# MCU.net
KiCad netlist of a schematic drawn in Altium Designer
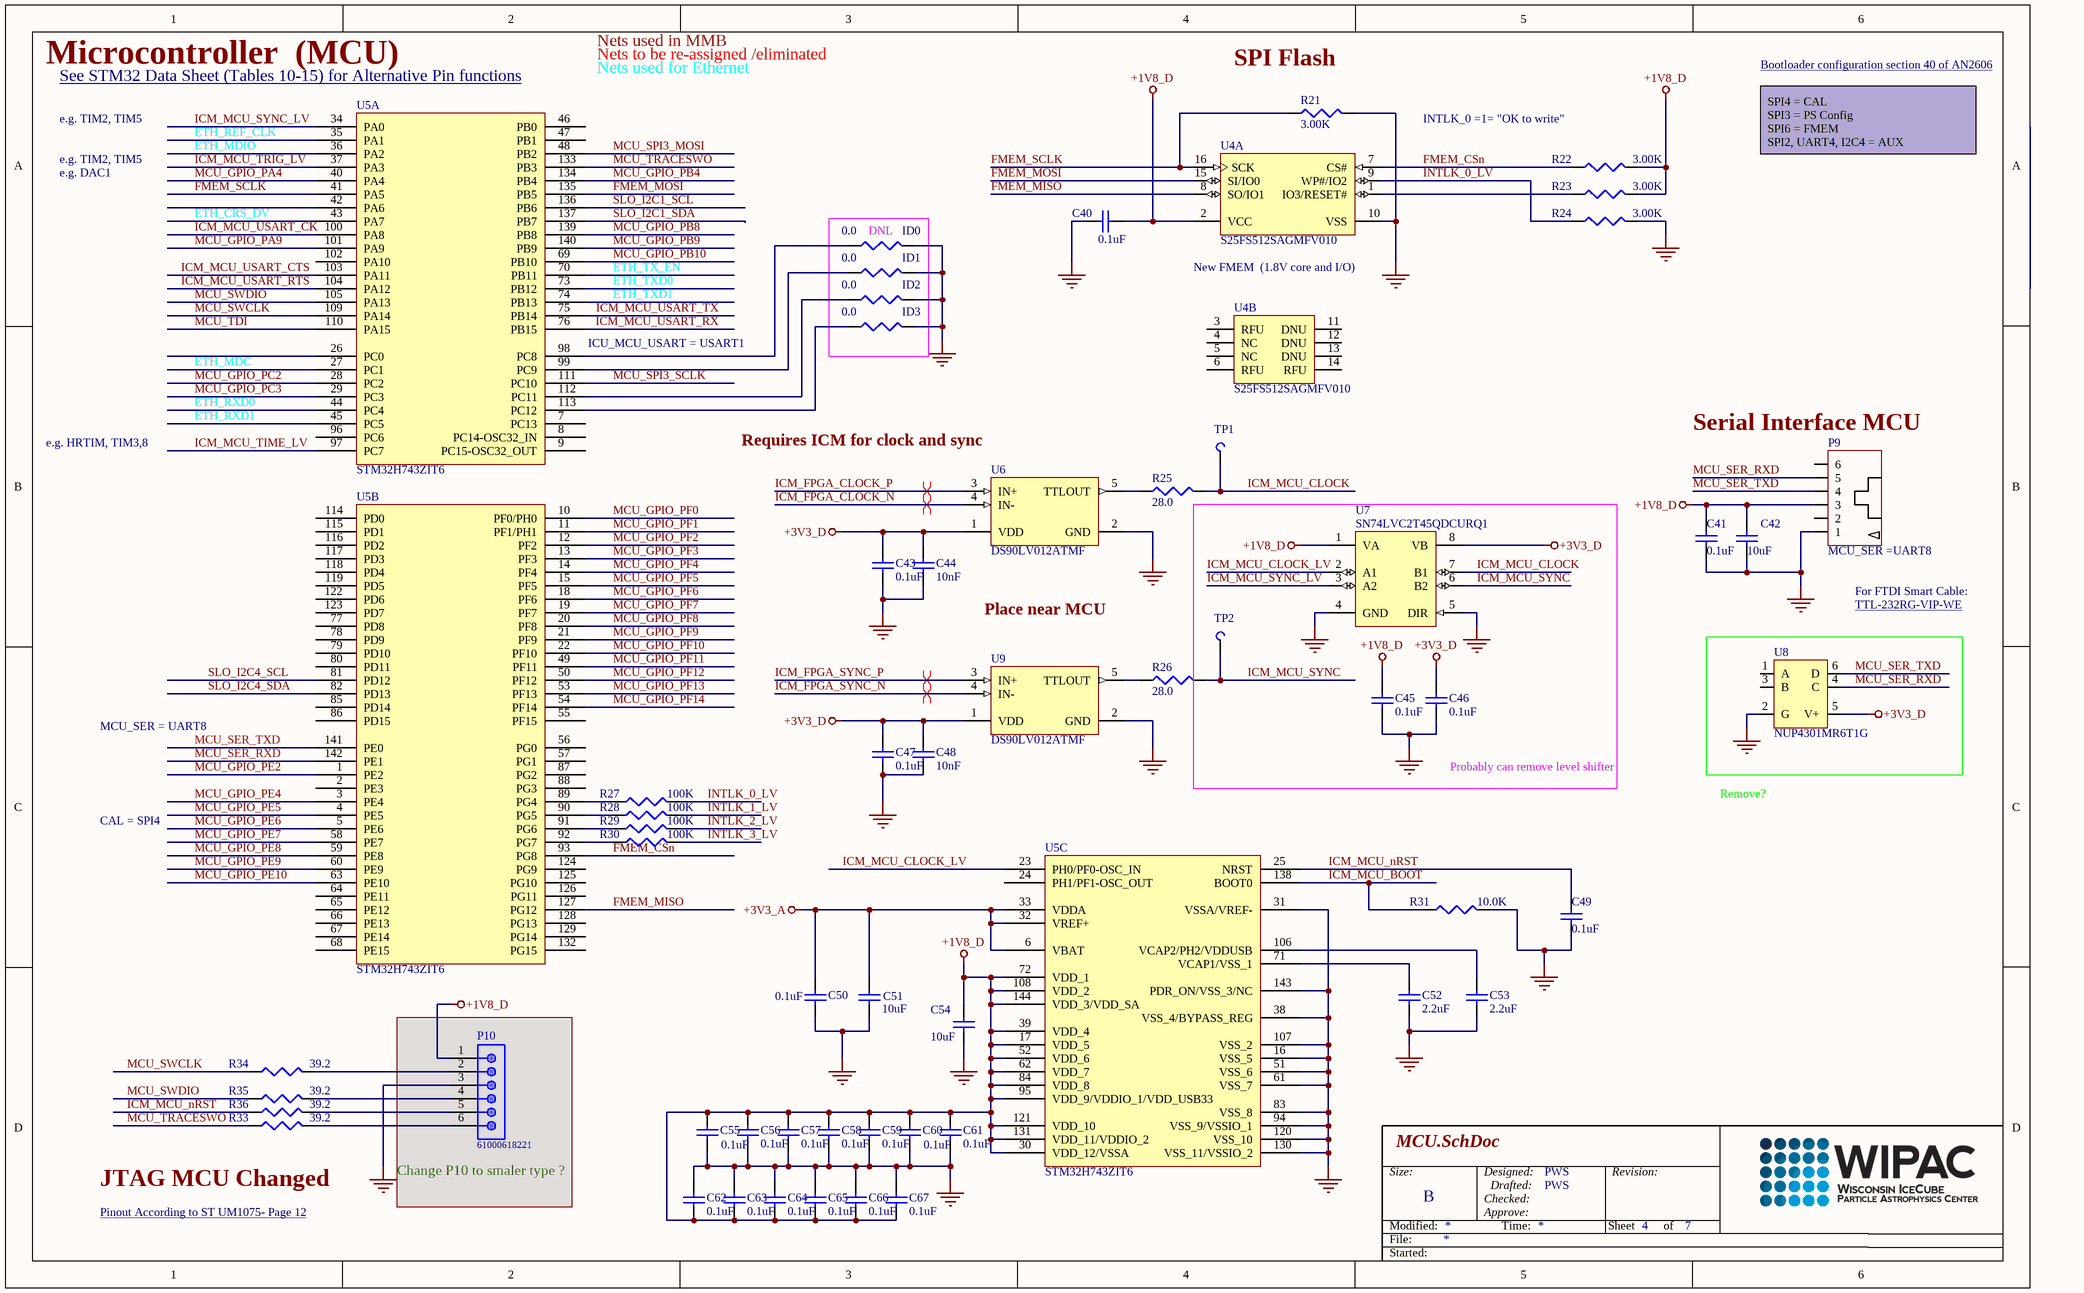
[diagram p0: MCU.SchDoc]

(export (version "E")
  (design (tool "Eeschema 10.0.6"))
  (components
    (comp (ref "C40")
      (value "0.1uF_603_50V")
      (footprint "CAPC_0603")
      (description "0.1µF ±10% 50V Ceramic Capacitor X7R 0603 (1608 Metric)")
      (fields
        (field (name "MANUFACTURER") "TDK")
        (field (name "MANUFACTURER PART NUMBER") "CGJ3E2X7R1H104K080AA")
        (field (name "CAPACITANCE") "0.1uF")
      )
      (libsource (lib "Custom1") (part "CapC_0.1uF_603_50V"))
    )
    (comp (ref "C41")
      (value "0.1uF_603_50V")
      (footprint "CAPC_0603")
      (description "0.1µF ±10% 50V Ceramic Capacitor X7R 0603 (1608 Metric)")
      (fields
        (field (name "MANUFACTURER") "Murata")
        (field (name "MANUFACTURER PART NUMBER") "GCJ188R71H104KA12D")
        (field (name "CAPACITANCE") "0.1uF")
      )
      (libsource (lib "Custom1") (part "CapC_0.1uF_603_50V_GCJ"))
    )
    (comp (ref "C42")
      (value "10uF_1206_16V")
      (footprint "CAPC_1206")
      (description "Capacitor")
      (fields
        (field (name "MANUFACTURER") "Murata")
        (field (name "MANUFACTURER PART NUMBER") "GCJ31CR71C106KA15L")
        (field (name "CAPACITANCE") "10uF")
      )
      (libsource (lib "Custom1") (part "CapC_10uF_1206_16V"))
    )
    (comp (ref "C43")
      (value "0.1uF_603_50V")
      (footprint "CAPC_0603")
      (description "0.1µF ±10% 50V Ceramic Capacitor X7R 0603 (1608 Metric)")
      (fields
        (field (name "MANUFACTURER") "TDK")
        (field (name "MANUFACTURER PART NUMBER") "CGJ3E2X7R1H104K080AA")
        (field (name "CAPACITANCE") "0.1uF")
      )
      (libsource (lib "Custom1") (part "CapC_0.1uF_603_50V"))
    )
    (comp (ref "C44")
      (value "10nF")
      (footprint "CAPC1608X90X35LL10T15")
      (description "Chip Capacitor, 10000 pF, +/- 10%, 16 V, -55 to 125 degC, 0603 (1608 Metric), RoHS, Tape and Reel")
      (fields (field (name "MANUFACTURER") "Murata"))
      (libsource (lib "Altium Content Vault") (part "CAP-NP-2"))
    )
    (comp (ref "C45")
      (value "0.1uF_603_50V")
      (footprint "CAPC_0603")
      (description "0.1µF ±10% 50V Ceramic Capacitor X7R 0603 (1608 Metric)")
      (fields
        (field (name "MANUFACTURER") "TDK")
        (field (name "MANUFACTURER PART NUMBER") "CGJ3E2X7R1H104K080AA")
        (field (name "CAPACITANCE") "0.1uF")
      )
      (libsource (lib "Custom1") (part "CapC_0.1uF_603_50V"))
    )
    (comp (ref "C46")
      (value "0.1uF_603_50V")
      (footprint "CAPC_0603")
      (description "0.1µF ±10% 50V Ceramic Capacitor X7R 0603 (1608 Metric)")
      (fields
        (field (name "MANUFACTURER") "TDK")
        (field (name "MANUFACTURER PART NUMBER") "CGJ3E2X7R1H104K080AA")
        (field (name "CAPACITANCE") "0.1uF")
      )
      (libsource (lib "Custom1") (part "CapC_0.1uF_603_50V"))
    )
    (comp (ref "C47")
      (value "0.1uF_603_50V")
      (footprint "CAPC_0603")
      (description "0.1µF ±10% 50V Ceramic Capacitor X7R 0603 (1608 Metric)")
      (fields
        (field (name "MANUFACTURER") "TDK")
        (field (name "MANUFACTURER PART NUMBER") "CGJ3E2X7R1H104K080AA")
        (field (name "CAPACITANCE") "0.1uF")
      )
      (libsource (lib "Custom1") (part "CapC_0.1uF_603_50V"))
    )
    (comp (ref "C48")
      (value "10nF")
      (footprint "CAPC1608X90X35LL10T15")
      (description "Chip Capacitor, 10000 pF, +/- 10%, 16 V, -55 to 125 degC, 0603 (1608 Metric), RoHS, Tape and Reel")
      (fields (field (name "MANUFACTURER") "Murata"))
      (libsource (lib "Altium Content Vault") (part "CAP-NP-2"))
    )
    (comp (ref "C49")
      (value "0.1uF_603_50V")
      (footprint "CAPC_0603")
      (description "0.1µF ±10% 50V Ceramic Capacitor X7R 0603 (1608 Metric)")
      (fields
        (field (name "MANUFACTURER") "Murata")
        (field (name "MANUFACTURER PART NUMBER") "GCJ188R71H104KA12D")
        (field (name "CAPACITANCE") "0.1uF")
      )
      (libsource (lib "Custom1") (part "CapC_0.1uF_603_50V_GCJ"))
    )
    (comp (ref "C50")
      (value "0.1uF_603_50V")
      (footprint "CAPC_0603")
      (description "0.1µF ±10% 50V Ceramic Capacitor X7R 0603 (1608 Metric)")
      (fields
        (field (name "MANUFACTURER") "TDK")
        (field (name "MANUFACTURER PART NUMBER") "CGJ3E2X7R1H104K080AA")
        (field (name "CAPACITANCE") "0.1uF")
      )
      (libsource (lib "Custom1") (part "CapC_0.1uF_603_50V"))
    )
    (comp (ref "C51")
      (value "10uF_805_10V")
      (footprint "CAPC_0805")
      (description "Capacitor")
      (fields
        (field (name "MANUFACTURER") "Murata")
        (field (name "MANUFACTURER PART NUMBER") "GCJ21BR71A106KE01L")
        (field (name "CAPACITANCE") "10uF")
      )
      (libsource (lib "Custom1") (part "CapC_10uF_805_10V"))
    )
    (comp (ref "C52")
      (value "2.2uF_805_16V")
      (footprint "CAPC_0805")
      (description "CAP CER 2.2UF 16V X7R 0805")
      (fields
        (field (name "MANUFACTURER") "Murata")
        (field (name "MANUFACTURER PART NUMBER") "GCJ21BR71C225KA13L")
        (field (name "CAPACITANCE") "2.2uF")
      )
      (libsource (lib "Custom1") (part "CapC_2.2uF_805_16V"))
    )
    (comp (ref "C53")
      (value "2.2uF_805_16V")
      (footprint "CAPC_0805")
      (description "CAP CER 2.2UF 16V X7R 0805")
      (fields
        (field (name "MANUFACTURER") "Murata")
        (field (name "MANUFACTURER PART NUMBER") "GCJ21BR71C225KA13L")
        (field (name "CAPACITANCE") "2.2uF")
      )
      (libsource (lib "Custom1") (part "CapC_2.2uF_805_16V"))
    )
    (comp (ref "C54")
      (value "10uF_805_10V")
      (footprint "CAPC_0805")
      (description "Capacitor")
      (fields
        (field (name "MANUFACTURER") "Murata")
        (field (name "MANUFACTURER PART NUMBER") "GCJ21BR71A106KE01L")
        (field (name "CAPACITANCE") "10uF")
      )
      (libsource (lib "Custom1") (part "CapC_10uF_805_10V"))
    )
    (comp (ref "C55")
      (value "0.1uF_603_50V")
      (footprint "CAPC_0603")
      (description "0.1µF ±10% 50V Ceramic Capacitor X7R 0603 (1608 Metric)")
      (fields
        (field (name "MANUFACTURER") "TDK")
        (field (name "MANUFACTURER PART NUMBER") "CGJ3E2X7R1H104K080AA")
        (field (name "CAPACITANCE") "0.1uF")
      )
      (libsource (lib "Custom1") (part "CapC_0.1uF_603_50V"))
    )
    (comp (ref "C56")
      (value "0.1uF_603_50V")
      (footprint "CAPC_0603")
      (description "0.1µF ±10% 50V Ceramic Capacitor X7R 0603 (1608 Metric)")
      (fields
        (field (name "MANUFACTURER") "TDK")
        (field (name "MANUFACTURER PART NUMBER") "CGJ3E2X7R1H104K080AA")
        (field (name "CAPACITANCE") "0.1uF")
      )
      (libsource (lib "Custom1") (part "CapC_0.1uF_603_50V"))
    )
    (comp (ref "C57")
      (value "0.1uF_603_50V")
      (footprint "CAPC_0603")
      (description "0.1µF ±10% 50V Ceramic Capacitor X7R 0603 (1608 Metric)")
      (fields
        (field (name "MANUFACTURER") "TDK")
        (field (name "MANUFACTURER PART NUMBER") "CGJ3E2X7R1H104K080AA")
        (field (name "CAPACITANCE") "0.1uF")
      )
      (libsource (lib "Custom1") (part "CapC_0.1uF_603_50V"))
    )
    (comp (ref "C58")
      (value "0.1uF_603_50V")
      (footprint "CAPC_0603")
      (description "0.1µF ±10% 50V Ceramic Capacitor X7R 0603 (1608 Metric)")
      (fields
        (field (name "MANUFACTURER") "TDK")
        (field (name "MANUFACTURER PART NUMBER") "CGJ3E2X7R1H104K080AA")
        (field (name "CAPACITANCE") "0.1uF")
      )
      (libsource (lib "Custom1") (part "CapC_0.1uF_603_50V"))
    )
    (comp (ref "C59")
      (value "0.1uF_603_50V")
      (footprint "CAPC_0603")
      (description "0.1µF ±10% 50V Ceramic Capacitor X7R 0603 (1608 Metric)")
      (fields
        (field (name "MANUFACTURER") "TDK")
        (field (name "MANUFACTURER PART NUMBER") "CGJ3E2X7R1H104K080AA")
        (field (name "CAPACITANCE") "0.1uF")
      )
      (libsource (lib "Custom1") (part "CapC_0.1uF_603_50V"))
    )
    (comp (ref "C60")
      (value "0.1uF_603_50V")
      (footprint "CAPC_0603")
      (description "0.1µF ±10% 50V Ceramic Capacitor X7R 0603 (1608 Metric)")
      (fields
        (field (name "MANUFACTURER") "TDK")
        (field (name "MANUFACTURER PART NUMBER") "CGJ3E2X7R1H104K080AA")
        (field (name "CAPACITANCE") "0.1uF")
      )
      (libsource (lib "Custom1") (part "CapC_0.1uF_603_50V"))
    )
    (comp (ref "C61")
      (value "0.1uF_603_50V")
      (footprint "CAPC_0603")
      (description "0.1µF ±10% 50V Ceramic Capacitor X7R 0603 (1608 Metric)")
      (fields
        (field (name "MANUFACTURER") "TDK")
        (field (name "MANUFACTURER PART NUMBER") "CGJ3E2X7R1H104K080AA")
        (field (name "CAPACITANCE") "0.1uF")
      )
      (libsource (lib "Custom1") (part "CapC_0.1uF_603_50V"))
    )
    (comp (ref "C62")
      (value "0.1uF_603_50V")
      (footprint "CAPC_0603")
      (description "0.1µF ±10% 50V Ceramic Capacitor X7R 0603 (1608 Metric)")
      (fields
        (field (name "MANUFACTURER") "TDK")
        (field (name "MANUFACTURER PART NUMBER") "CGJ3E2X7R1H104K080AA")
        (field (name "CAPACITANCE") "0.1uF")
      )
      (libsource (lib "Custom1") (part "CapC_0.1uF_603_50V"))
    )
    (comp (ref "C63")
      (value "0.1uF_603_50V")
      (footprint "CAPC_0603")
      (description "0.1µF ±10% 50V Ceramic Capacitor X7R 0603 (1608 Metric)")
      (fields
        (field (name "MANUFACTURER") "TDK")
        (field (name "MANUFACTURER PART NUMBER") "CGJ3E2X7R1H104K080AA")
        (field (name "CAPACITANCE") "0.1uF")
      )
      (libsource (lib "Custom1") (part "CapC_0.1uF_603_50V"))
    )
    (comp (ref "C64")
      (value "0.1uF_603_50V")
      (footprint "CAPC_0603")
      (description "0.1µF ±10% 50V Ceramic Capacitor X7R 0603 (1608 Metric)")
      (fields
        (field (name "MANUFACTURER") "TDK")
        (field (name "MANUFACTURER PART NUMBER") "CGJ3E2X7R1H104K080AA")
        (field (name "CAPACITANCE") "0.1uF")
      )
      (libsource (lib "Custom1") (part "CapC_0.1uF_603_50V"))
    )
    (comp (ref "C65")
      (value "0.1uF_603_50V")
      (footprint "CAPC_0603")
      (description "0.1µF ±10% 50V Ceramic Capacitor X7R 0603 (1608 Metric)")
      (fields
        (field (name "MANUFACTURER") "TDK")
        (field (name "MANUFACTURER PART NUMBER") "CGJ3E2X7R1H104K080AA")
        (field (name "CAPACITANCE") "0.1uF")
      )
      (libsource (lib "Custom1") (part "CapC_0.1uF_603_50V"))
    )
    (comp (ref "C66")
      (value "0.1uF_603_50V")
      (footprint "CAPC_0603")
      (description "0.1µF ±10% 50V Ceramic Capacitor X7R 0603 (1608 Metric)")
      (fields
        (field (name "MANUFACTURER") "TDK")
        (field (name "MANUFACTURER PART NUMBER") "CGJ3E2X7R1H104K080AA")
        (field (name "CAPACITANCE") "0.1uF")
      )
      (libsource (lib "Custom1") (part "CapC_0.1uF_603_50V"))
    )
    (comp (ref "C67")
      (value "0.1uF_603_50V")
      (footprint "CAPC_0603")
      (description "0.1µF ±10% 50V Ceramic Capacitor X7R 0603 (1608 Metric)")
      (fields
        (field (name "MANUFACTURER") "TDK")
        (field (name "MANUFACTURER PART NUMBER") "CGJ3E2X7R1H104K080AA")
        (field (name "CAPACITANCE") "0.1uF")
      )
      (libsource (lib "Custom1") (part "CapC_0.1uF_603_50V"))
    )
    (comp (ref "ID0")
      (value "R_ZERO_805")
      (footprint "RES_0603")
      (description "RES ZERO OHM 0805 SMD")
      (fields
        (field (name "MANUFACTURER") "Panasonic")
        (field (name "MANUFACTURER PART NUMBER") "ERJ6GEY0R00V")
        (field (name "RESISTANCE") "0.0")
      )
      (libsource (lib "Custom1") (part "R_ZERO_805"))
    )
    (comp (ref "ID1")
      (value "R_ZERO_805")
      (footprint "RES_0603")
      (description "RES ZERO OHM 0805 SMD")
      (fields
        (field (name "MANUFACTURER") "Panasonic")
        (field (name "MANUFACTURER PART NUMBER") "ERJ6GEY0R00V")
        (field (name "RESISTANCE") "0.0")
      )
      (libsource (lib "Custom1") (part "R_ZERO_805"))
    )
    (comp (ref "ID2")
      (value "R_ZERO_805")
      (footprint "RES_0603")
      (description "RES ZERO OHM 0805 SMD")
      (fields
        (field (name "MANUFACTURER") "Panasonic")
        (field (name "MANUFACTURER PART NUMBER") "ERJ6GEY0R00V")
        (field (name "RESISTANCE") "0.0")
      )
      (libsource (lib "Custom1") (part "R_ZERO_805"))
    )
    (comp (ref "ID3")
      (value "R_ZERO_805")
      (footprint "RES_0603")
      (description "RES ZERO OHM 0805 SMD")
      (fields
        (field (name "MANUFACTURER") "Panasonic")
        (field (name "MANUFACTURER PART NUMBER") "ERJ6GEY0R00V")
        (field (name "RESISTANCE") "0.0")
      )
      (libsource (lib "Custom1") (part "R_ZERO_805"))
    )
    (comp (ref "P9")
      (value "MCU_SER =UART8")
      (footprint "Header Male 6 Vert")
      (description "CONN HEADER 6POS .100 VERT 30AU")
      (fields (field (name "MANUFACTURER") "Molex") (field (name "MANUFACTURER PART NUMBER") "0705430110"))
      (libsource (lib "Custom1") (part "Header Male SL-6-VERT"))
    )
    (comp (ref "P10")
      (value "61000618221")
      (footprint "61000618221")
      (description "WR-PHD Pin Header, SMT, pitch 2.54mm, Single Row, Vertical, 6pin")
      (fields (field (name "PUBLISHER") "Wurth Elektronik"))
      (libsource (lib "WR-PHD") (part "61000618221"))
    )
    (comp (ref "R21")
      (value "R_3.00K_603_1%")
      (footprint "RES_0603")
      (description "RES 3.00K OHM 1/10W 1% 0603 SMD")
      (fields
        (field (name "MANUFACTURER") "Panasonic")
        (field (name "MANUFACTURER PART NUMBER") "ERJ3EKF3001V")
        (field (name "RESISTANCE") "3.00K")
      )
      (libsource (lib "Custom1") (part "R_3.00K_603_1%"))
    )
    (comp (ref "R22")
      (value "R_3.00K_603_1%")
      (footprint "RES_0603")
      (description "RES 3.00K OHM 1/10W 1% 0603 SMD")
      (fields
        (field (name "MANUFACTURER") "Panasonic")
        (field (name "MANUFACTURER PART NUMBER") "ERJ3EKF3001V")
        (field (name "RESISTANCE") "3.00K")
      )
      (libsource (lib "Custom1") (part "R_3.00K_603_1%"))
    )
    (comp (ref "R23")
      (value "R_3.00K_603_1%")
      (footprint "RES_0603")
      (description "RES 3.00K OHM 1/10W 1% 0603 SMD")
      (fields
        (field (name "MANUFACTURER") "Panasonic")
        (field (name "MANUFACTURER PART NUMBER") "ERJ3EKF3001V")
        (field (name "RESISTANCE") "3.00K")
      )
      (libsource (lib "Custom1") (part "R_3.00K_603_1%"))
    )
    (comp (ref "R24")
      (value "R_3.00K_603_1%")
      (footprint "RES_0603")
      (description "RES 3.00K OHM 1/10W 1% 0603 SMD")
      (fields
        (field (name "MANUFACTURER") "Panasonic")
        (field (name "MANUFACTURER PART NUMBER") "ERJ3EKF3001V")
        (field (name "RESISTANCE") "3.00K")
      )
      (libsource (lib "Custom1") (part "R_3.00K_603_1%"))
    )
    (comp (ref "R25")
      (value "R_28.0_603_1%")
      (footprint "RES_0603")
      (description "RES 28.0 OHM 1/10W 1% 0603 SMD")
      (fields
        (field (name "MANUFACTURER") "Panasonic")
        (field (name "MANUFACTURER PART NUMBER") "ERJ3EKF28R0V")
        (field (name "RESISTANCE") "28.0")
      )
      (libsource (lib "Custom1") (part "R_28.0_603_1%"))
    )
    (comp (ref "R26")
      (value "R_28.0_603_1%")
      (footprint "RES_0603")
      (description "RES 28.0 OHM 1/10W 1% 0603 SMD")
      (fields
        (field (name "MANUFACTURER") "Panasonic")
        (field (name "MANUFACTURER PART NUMBER") "ERJ3EKF28R0V")
        (field (name "RESISTANCE") "28.0")
      )
      (libsource (lib "Custom1") (part "R_28.0_603_1%"))
    )
    (comp (ref "R27")
      (value "R_100K_603_1%")
      (footprint "RES_0603")
      (description "RES 100K OHM 1/10W 1% 0603 SMD")
      (fields
        (field (name "MANUFACTURER") "Panasonic")
        (field (name "MANUFACTURER PART NUMBER") "ERJ3EKF1003V")
        (field (name "RESISTANCE") "100K")
      )
      (libsource (lib "Custom1") (part "R_100K_603_1%"))
    )
    (comp (ref "R28")
      (value "R_100K_603_1%")
      (footprint "RES_0603")
      (description "RES 100K OHM 1/10W 1% 0603 SMD")
      (fields
        (field (name "MANUFACTURER") "Panasonic")
        (field (name "MANUFACTURER PART NUMBER") "ERJ3EKF1003V")
        (field (name "RESISTANCE") "100K")
      )
      (libsource (lib "Custom1") (part "R_100K_603_1%"))
    )
    (comp (ref "R29")
      (value "R_100K_603_1%")
      (footprint "RES_0603")
      (description "RES 100K OHM 1/10W 1% 0603 SMD")
      (fields
        (field (name "MANUFACTURER") "Panasonic")
        (field (name "MANUFACTURER PART NUMBER") "ERJ3EKF1003V")
        (field (name "RESISTANCE") "100K")
      )
      (libsource (lib "Custom1") (part "R_100K_603_1%"))
    )
    (comp (ref "R30")
      (value "R_100K_603_1%")
      (footprint "RES_0603")
      (description "RES 100K OHM 1/10W 1% 0603 SMD")
      (fields
        (field (name "MANUFACTURER") "Panasonic")
        (field (name "MANUFACTURER PART NUMBER") "ERJ3EKF1003V")
        (field (name "RESISTANCE") "100K")
      )
      (libsource (lib "Custom1") (part "R_100K_603_1%"))
    )
    (comp (ref "R31")
      (value "10.0K")
      (footprint "RES_0603")
      (description "RES 10.0K OHM 1/10W 1% 0603 SMD")
      (fields
        (field (name "MANUFACTURER") "Panasonic")
        (field (name "MANUFACTURER PART NUMBER") "ERJ3EKF1002V")
      )
      (libsource (lib "Custom1") (part "R_10.0K_603_1%"))
    )
    (comp (ref "R33")
      (value "R_39.2_603_1%")
      (footprint "RES_0603")
      (description "RES 39.2 OHM 1/10W 1% 0603 SMD")
      (fields
        (field (name "MANUFACTURER") "Panasonic")
        (field (name "MANUFACTURER PART NUMBER") "ERJ-3EKF39R2V")
        (field (name "RESISTANCE") "39.2")
      )
      (libsource (lib "Custom1") (part "R_39.2_603_1%"))
    )
    (comp (ref "R34")
      (value "R_39.2_603_1%")
      (footprint "RES_0603")
      (description "RES 39.2 OHM 1/10W 1% 0603 SMD")
      (fields
        (field (name "MANUFACTURER") "Panasonic")
        (field (name "MANUFACTURER PART NUMBER") "ERJ-3EKF39R2V")
        (field (name "RESISTANCE") "39.2")
      )
      (libsource (lib "Custom1") (part "R_39.2_603_1%"))
    )
    (comp (ref "R35")
      (value "R_39.2_603_1%")
      (footprint "RES_0603")
      (description "RES 39.2 OHM 1/10W 1% 0603 SMD")
      (fields
        (field (name "MANUFACTURER") "Panasonic")
        (field (name "MANUFACTURER PART NUMBER") "ERJ-3EKF39R2V")
        (field (name "RESISTANCE") "39.2")
      )
      (libsource (lib "Custom1") (part "R_39.2_603_1%"))
    )
    (comp (ref "R36")
      (value "R_39.2_603_1%")
      (footprint "RES_0603")
      (description "RES 39.2 OHM 1/10W 1% 0603 SMD")
      (fields
        (field (name "MANUFACTURER") "Panasonic")
        (field (name "MANUFACTURER PART NUMBER") "ERJ-3EKF39R2V")
        (field (name "RESISTANCE") "39.2")
      )
      (libsource (lib "Custom1") (part "R_39.2_603_1%"))
    )
    (comp (ref "TP1")
      (value "PC TEST POINT MINI SMD")
      (footprint "Test Point SM")
      (description "5019KCT-ND")
      (fields
        (field (name "MANUFACTURER") "Keystone Electronics")
        (field (name "MANUFACTURER PART NUMBER") "5019")
      )
      (libsource (lib "Custom1") (part "Test Point SM"))
    )
    (comp (ref "TP2")
      (value "PC TEST POINT MINI SMD")
      (footprint "Test Point SM")
      (description "5019KCT-ND")
      (fields
        (field (name "MANUFACTURER") "Keystone Electronics")
        (field (name "MANUFACTURER PART NUMBER") "5019")
      )
      (libsource (lib "Custom1") (part "Test Point SM"))
    )
    (comp (ref "U4")
      (value "S25FS512SAGMFV010")
      (footprint "MICT-SF-16_N")
      (description "IC FLASH 512M SPI 133MHZ 16SOIC")
      (fields (field (name "MANUFACTURER") "Cypress"))
      (libsource (lib "Custom1") (part "S25FS512SAGMFV010"))
    )
    (comp (ref "U5")
      (value "STM32H743ZIT6")
      (footprint "STM-LQFP144_N")
      (description "ARM® Cortex®-M7 STM32H7 Microcontroller IC 32-Bit 400MHz 2MB (2M x 8) FLASH 144-LQFP (20x20)")
      (fields (field (name "MANUFACTURER") "STMicroelectronics"))
      (libsource (lib "Custom1") (part "STM32H743ZIT6"))
    )
    (comp (ref "U6")
      (value "DS90LV012ATMF")
      (footprint "MF05A_N")
      (description "3V LVDS Single CMOS Differential Line Receiver, 5-pin SOT-23")
      (fields
        (field (name "MANUFACTURER") "TI National Semiconductor")
        (field (name "MANUFACTURER PART NUMBER") "DS90LV012ATMF/NOPB")
      )
      (libsource (lib "Custom1") (part "DS90LV012ATMF"))
    )
    (comp (ref "U7")
      (value "SN74LVC2T45QDCURQ1")
      (footprint "TI-DGK8_N")
      (description "Voltage Level Translator Bidirectional 1 Circuit 2 Channel 420Mbps SM8 (SSOP)")
      (fields
        (field (name "GENERIC PART NUMBER") "SN74LVC2T45-Q1")
        (field (name "MANUFACTURER") "Texas Instruments")
      )
      (libsource (lib "Custom1") (part "SN74LVC2T45QDCURQ1"))
    )
    (comp (ref "U8")
      (value "NUP4301MR6T1G")
      (footprint "ONSC-SC-74-6-318F-05_V")
      (fields (field (name "MANUFACTURER") "ON Semiconductor"))
      (libsource (lib "Custom1") (part "NUP4301MR6T1G"))
    )
    (comp (ref "U9")
      (value "DS90LV012ATMF")
      (footprint "MF05A_N")
      (description "3V LVDS Single CMOS Differential Line Receiver, 5-pin SOT-23")
      (fields
        (field (name "MANUFACTURER") "TI National Semiconductor")
        (field (name "MANUFACTURER PART NUMBER") "DS90LV012ATMF/NOPB")
      )
      (libsource (lib "Custom1") (part "DS90LV012ATMF"))
    )
  )
  (nets
    (net (code "1") (name "+1V8_D") (class "Default")
      (node (ref "C40") (pin "1") (pinfunction "1_1") (pintype "passive"))
      (node (ref "C41") (pin "2") (pinfunction "2_2") (pintype "passive"))
      (node (ref "C42") (pin "2") (pinfunction "2_2") (pintype "passive"))
      (node (ref "C45") (pin "2") (pinfunction "2_2") (pintype "passive"))
      (node (ref "C54") (pin "2") (pinfunction "2_2") (pintype "passive"))
      (node (ref "C55") (pin "2") (pinfunction "2_2") (pintype "passive"))
      (node (ref "C56") (pin "2") (pinfunction "2_2") (pintype "passive"))
      (node (ref "C57") (pin "2") (pinfunction "2_2") (pintype "passive"))
      (node (ref "C58") (pin "2") (pinfunction "2_2") (pintype "passive"))
      (node (ref "C59") (pin "2") (pinfunction "2_2") (pintype "passive"))
      (node (ref "C60") (pin "2") (pinfunction "2_2") (pintype "passive"))
      (node (ref "C61") (pin "2") (pinfunction "2_2") (pintype "passive"))
      (node (ref "C62") (pin "1") (pinfunction "1_1") (pintype "passive"))
      (node (ref "C63") (pin "1") (pinfunction "1_1") (pintype "passive"))
      (node (ref "C64") (pin "1") (pinfunction "1_1") (pintype "passive"))
      (node (ref "C65") (pin "1") (pinfunction "1_1") (pintype "passive"))
      (node (ref "C66") (pin "1") (pinfunction "1_1") (pintype "passive"))
      (node (ref "C67") (pin "1") (pinfunction "1_1") (pintype "passive"))
      (node (ref "P10") (pin "1") (pinfunction "1_1") (pintype "passive"))
      (node (ref "P9") (pin "3") (pinfunction "3_3") (pintype "passive"))
      (node (ref "R22") (pin "2") (pinfunction "2_2") (pintype "passive"))
      (node (ref "R23") (pin "2") (pinfunction "2_2") (pintype "passive"))
      (node (ref "U4") (pin "2") (pinfunction "VCC_2") (pintype "power_in"))
      (node (ref "U5") (pin "108") (pinfunction "VDD_2_108") (pintype "passive"))
      (node (ref "U5") (pin "121") (pinfunction "VDD_10_121") (pintype "passive"))
      (node (ref "U5") (pin "131") (pinfunction "VDD_11/VDDIO_2_131") (pintype "passive"))
      (node (ref "U5") (pin "144") (pinfunction "VDD_3/VDD_SA_144") (pintype "passive"))
      (node (ref "U5") (pin "17") (pinfunction "VDD_5_17") (pintype "passive"))
      (node (ref "U5") (pin "30") (pinfunction "VDD_12/VSSA_30") (pintype "passive"))
      (node (ref "U5") (pin "39") (pinfunction "VDD_4_39") (pintype "passive"))
      (node (ref "U5") (pin "52") (pinfunction "VDD_6_52") (pintype "passive"))
      (node (ref "U5") (pin "62") (pinfunction "VDD_7_62") (pintype "passive"))
      (node (ref "U5") (pin "72") (pinfunction "VDD_1_72") (pintype "passive"))
      (node (ref "U5") (pin "84") (pinfunction "VDD_8_84") (pintype "passive"))
      (node (ref "U5") (pin "95") (pinfunction "VDD_9/VDDIO_1/VDD_USB33_95") (pintype "passive"))
      (node (ref "U7") (pin "1") (pinfunction "VA_1") (pintype "power_in"))
    )
    (net (code "2") (name "+3V3_A") (class "Default")
      (node (ref "C50") (pin "2") (pinfunction "2_2") (pintype "passive"))
      (node (ref "C51") (pin "2") (pinfunction "2_2") (pintype "passive"))
      (node (ref "U5") (pin "32") (pinfunction "VREF+_32") (pintype "passive"))
      (node (ref "U5") (pin "33") (pinfunction "VDDA_33") (pintype "passive"))
      (node (ref "U5") (pin "6") (pinfunction "VBAT_6") (pintype "passive"))
    )
    (net (code "3") (name "+3V3_D") (class "Default")
      (node (ref "C43") (pin "2") (pinfunction "2_2") (pintype "passive"))
      (node (ref "C44") (pin "2") (pinfunction "2_2") (pintype "passive"))
      (node (ref "C46") (pin "2") (pinfunction "2_2") (pintype "passive"))
      (node (ref "C47") (pin "2") (pinfunction "2_2") (pintype "passive"))
      (node (ref "C48") (pin "2") (pinfunction "2_2") (pintype "passive"))
      (node (ref "U6") (pin "1") (pinfunction "VDD_1") (pintype "power_in"))
      (node (ref "U7") (pin "8") (pinfunction "VB_8") (pintype "power_in"))
      (node (ref "U8") (pin "5") (pinfunction "V+_5") (pintype "power_in"))
      (node (ref "U9") (pin "1") (pinfunction "VDD_1") (pintype "power_in"))
    )
    (net (code "4") (name "/ETH_CRS_DV") (class "Default")
      (node (ref "U5") (pin "43") (pinfunction "PA7_43") (pintype "passive"))
    )
    (net (code "5") (name "/ETH_MDC") (class "Default")
      (node (ref "U5") (pin "27") (pinfunction "PC1_27") (pintype "passive"))
    )
    (net (code "6") (name "/ETH_MDIO") (class "Default")
      (node (ref "U5") (pin "36") (pinfunction "PA2_36") (pintype "passive"))
    )
    (net (code "7") (name "/ETH_REF_CLK") (class "Default")
      (node (ref "U5") (pin "35") (pinfunction "PA1_35") (pintype "passive"))
    )
    (net (code "8") (name "/ETH_RXD0") (class "Default")
      (node (ref "U5") (pin "44") (pinfunction "PC4_44") (pintype "passive"))
    )
    (net (code "9") (name "/ETH_RXD1") (class "Default")
      (node (ref "U5") (pin "45") (pinfunction "PC5_45") (pintype "passive"))
    )
    (net (code "10") (name "/ETH_TXD0") (class "Default")
      (node (ref "U5") (pin "73") (pinfunction "PB12_73") (pintype "passive"))
    )
    (net (code "11") (name "/ETH_TXD1") (class "Default")
      (node (ref "U5") (pin "74") (pinfunction "PB13_74") (pintype "passive"))
    )
    (net (code "12") (name "/ETH_TX_EN") (class "Default")
      (node (ref "U5") (pin "70") (pinfunction "PB11_70") (pintype "passive"))
    )
    (net (code "13") (name "/FMEM_CSn") (class "Default")
      (node (ref "R22") (pin "1") (pinfunction "1_1") (pintype "passive"))
      (node (ref "U4") (pin "7") (pinfunction "CS#_7") (pintype "input"))
      (node (ref "U5") (pin "93") (pinfunction "PG8_93") (pintype "passive"))
    )
    (net (code "14") (name "/FMEM_MISO") (class "Default")
      (node (ref "U4") (pin "8") (pinfunction "SO/IO1_8") (pintype "bidirectional"))
      (node (ref "U5") (pin "127") (pinfunction "PG12_127") (pintype "passive"))
    )
    (net (code "15") (name "/FMEM_MOSI") (class "Default")
      (node (ref "U4") (pin "15") (pinfunction "SI/IO0_15") (pintype "bidirectional"))
      (node (ref "U5") (pin "135") (pinfunction "PB5_135") (pintype "passive"))
    )
    (net (code "16") (name "/FMEM_SCLK") (class "Default")
      (node (ref "R21") (pin "1") (pinfunction "1_1") (pintype "passive"))
      (node (ref "U4") (pin "16") (pinfunction "SCK_16") (pintype "input"))
      (node (ref "U5") (pin "41") (pinfunction "PA5_41") (pintype "passive"))
    )
    (net (code "17") (name "/ICM_FPGA_CLOCK_N") (class "Default")
      (node (ref "U6") (pin "4") (pinfunction "IN-_4") (pintype "input"))
    )
    (net (code "18") (name "/ICM_FPGA_CLOCK_P") (class "Default")
      (node (ref "U6") (pin "3") (pinfunction "IN+_3") (pintype "input"))
    )
    (net (code "19") (name "/ICM_FPGA_SYNC_N") (class "Default")
      (node (ref "U9") (pin "4") (pinfunction "IN-_4") (pintype "input"))
    )
    (net (code "20") (name "/ICM_FPGA_SYNC_P") (class "Default")
      (node (ref "U9") (pin "3") (pinfunction "IN+_3") (pintype "input"))
    )
    (net (code "21") (name "/ICM_MCU_BOOT") (class "Default")
      (node (ref "R31") (pin "1") (pinfunction "1_1") (pintype "passive"))
      (node (ref "U5") (pin "138") (pinfunction "BOOT0_138") (pintype "passive"))
    )
    (net (code "22") (name "/ICM_MCU_CLOCK") (class "Default")
      (node (ref "R25") (pin "2") (pinfunction "2_2") (pintype "passive"))
      (node (ref "TP1") (pin "1") (pinfunction "1_1") (pintype "passive"))
      (node (ref "U7") (pin "7") (pinfunction "B1_7") (pintype "bidirectional"))
    )
    (net (code "23") (name "/ICM_MCU_CLOCK_LV") (class "Default")
      (node (ref "U5") (pin "23") (pinfunction "PH0/PF0-OSC_IN_23") (pintype "passive"))
      (node (ref "U7") (pin "2") (pinfunction "A1_2") (pintype "bidirectional"))
    )
    (net (code "24") (name "/ICM_MCU_SYNC") (class "Default")
      (node (ref "R26") (pin "2") (pinfunction "2_2") (pintype "passive"))
      (node (ref "TP2") (pin "1") (pinfunction "1_1") (pintype "passive"))
      (node (ref "U7") (pin "6") (pinfunction "B2_6") (pintype "bidirectional"))
    )
    (net (code "25") (name "/ICM_MCU_SYNC_LV") (class "Default")
      (node (ref "U5") (pin "34") (pinfunction "PA0_34") (pintype "passive"))
      (node (ref "U7") (pin "3") (pinfunction "A2_3") (pintype "bidirectional"))
    )
    (net (code "26") (name "/ICM_MCU_TIME_LV") (class "Default")
      (node (ref "U5") (pin "97") (pinfunction "PC7_97") (pintype "passive"))
    )
    (net (code "27") (name "/ICM_MCU_TRIG_LV") (class "Default")
      (node (ref "U5") (pin "37") (pinfunction "PA3_37") (pintype "passive"))
    )
    (net (code "28") (name "/ICM_MCU_USART_CK") (class "Default")
      (node (ref "U5") (pin "100") (pinfunction "PA8_100") (pintype "passive"))
    )
    (net (code "29") (name "/ICM_MCU_USART_CTS") (class "Default")
      (node (ref "U5") (pin "103") (pinfunction "PA11_103") (pintype "passive"))
    )
    (net (code "30") (name "/ICM_MCU_USART_RTS") (class "Default")
      (node (ref "U5") (pin "104") (pinfunction "PA12_104") (pintype "passive"))
    )
    (net (code "31") (name "/ICM_MCU_USART_RX") (class "Default")
      (node (ref "U5") (pin "76") (pinfunction "PB15_76") (pintype "passive"))
    )
    (net (code "32") (name "/ICM_MCU_USART_TX") (class "Default")
      (node (ref "U5") (pin "75") (pinfunction "PB14_75") (pintype "passive"))
    )
    (net (code "33") (name "/ICM_MCU_nRST") (class "Default")
      (node (ref "C49") (pin "2") (pinfunction "2_2") (pintype "passive"))
      (node (ref "R36") (pin "1") (pinfunction "1_1") (pintype "passive"))
      (node (ref "U5") (pin "25") (pinfunction "NRST_25") (pintype "passive"))
    )
    (net (code "34") (name "/INTLK_0_LV") (class "Default")
      (node (ref "R24") (pin "1") (pinfunction "1_1") (pintype "passive"))
      (node (ref "R27") (pin "2") (pinfunction "2_2") (pintype "passive"))
      (node (ref "U4") (pin "9") (pinfunction "WP#/IO2_9") (pintype "bidirectional"))
    )
    (net (code "35") (name "/INTLK_1_LV") (class "Default")
      (node (ref "R28") (pin "2") (pinfunction "2_2") (pintype "passive"))
    )
    (net (code "36") (name "/INTLK_2_LV") (class "Default")
      (node (ref "R29") (pin "2") (pinfunction "2_2") (pintype "passive"))
    )
    (net (code "37") (name "/INTLK_3_LV") (class "Default")
      (node (ref "R30") (pin "2") (pinfunction "2_2") (pintype "passive"))
    )
    (net (code "38") (name "/MCU_GPIO_PA4") (class "Default")
      (node (ref "U5") (pin "40") (pinfunction "PA4_40") (pintype "passive"))
    )
    (net (code "39") (name "/MCU_GPIO_PA9") (class "Default")
      (node (ref "U5") (pin "101") (pinfunction "PA9_101") (pintype "passive"))
    )
    (net (code "40") (name "/MCU_GPIO_PB4") (class "Default")
      (node (ref "U5") (pin "134") (pinfunction "PB4_134") (pintype "passive"))
    )
    (net (code "41") (name "/MCU_GPIO_PB8") (class "Default")
      (node (ref "U5") (pin "139") (pinfunction "PB8_139") (pintype "passive"))
    )
    (net (code "42") (name "/MCU_GPIO_PB9") (class "Default")
      (node (ref "U5") (pin "140") (pinfunction "PB9_140") (pintype "passive"))
    )
    (net (code "43") (name "/MCU_GPIO_PB10") (class "Default")
      (node (ref "U5") (pin "69") (pinfunction "PB10_69") (pintype "passive"))
    )
    (net (code "44") (name "/MCU_GPIO_PC2") (class "Default")
      (node (ref "U5") (pin "28") (pinfunction "PC2_28") (pintype "passive"))
    )
    (net (code "45") (name "/MCU_GPIO_PC3") (class "Default")
      (node (ref "U5") (pin "29") (pinfunction "PC3_29") (pintype "passive"))
    )
    (net (code "46") (name "/MCU_GPIO_PE2") (class "Default")
      (node (ref "U5") (pin "1") (pinfunction "PE2_1") (pintype "passive"))
    )
    (net (code "47") (name "/MCU_GPIO_PE4") (class "Default")
      (node (ref "U5") (pin "3") (pinfunction "PE4_3") (pintype "passive"))
    )
    (net (code "48") (name "/MCU_GPIO_PE5") (class "Default")
      (node (ref "U5") (pin "4") (pinfunction "PE5_4") (pintype "passive"))
    )
    (net (code "49") (name "/MCU_GPIO_PE6") (class "Default")
      (node (ref "U5") (pin "5") (pinfunction "PE6_5") (pintype "passive"))
    )
    (net (code "50") (name "/MCU_GPIO_PE7") (class "Default")
      (node (ref "U5") (pin "58") (pinfunction "PE7_58") (pintype "passive"))
    )
    (net (code "51") (name "/MCU_GPIO_PE8") (class "Default")
      (node (ref "U5") (pin "59") (pinfunction "PE8_59") (pintype "passive"))
    )
    (net (code "52") (name "/MCU_GPIO_PE9") (class "Default")
      (node (ref "U5") (pin "60") (pinfunction "PE9_60") (pintype "passive"))
    )
    (net (code "53") (name "/MCU_GPIO_PE10") (class "Default")
      (node (ref "U5") (pin "63") (pinfunction "PE10_63") (pintype "passive"))
    )
    (net (code "54") (name "/MCU_GPIO_PF0") (class "Default")
      (node (ref "U5") (pin "10") (pinfunction "PF0/PH0_10") (pintype "passive"))
    )
    (net (code "55") (name "/MCU_GPIO_PF1") (class "Default")
      (node (ref "U5") (pin "11") (pinfunction "PF1/PH1_11") (pintype "passive"))
    )
    (net (code "56") (name "/MCU_GPIO_PF2") (class "Default")
      (node (ref "U5") (pin "12") (pinfunction "PF2_12") (pintype "passive"))
    )
    (net (code "57") (name "/MCU_GPIO_PF3") (class "Default")
      (node (ref "U5") (pin "13") (pinfunction "PF3_13") (pintype "passive"))
    )
    (net (code "58") (name "/MCU_GPIO_PF4") (class "Default")
      (node (ref "U5") (pin "14") (pinfunction "PF4_14") (pintype "passive"))
    )
    (net (code "59") (name "/MCU_GPIO_PF5") (class "Default")
      (node (ref "U5") (pin "15") (pinfunction "PF5_15") (pintype "passive"))
    )
    (net (code "60") (name "/MCU_GPIO_PF6") (class "Default")
      (node (ref "U5") (pin "18") (pinfunction "PF6_18") (pintype "passive"))
    )
    (net (code "61") (name "/MCU_GPIO_PF7") (class "Default")
      (node (ref "U5") (pin "19") (pinfunction "PF7_19") (pintype "passive"))
    )
    (net (code "62") (name "/MCU_GPIO_PF8") (class "Default")
      (node (ref "U5") (pin "20") (pinfunction "PF8_20") (pintype "passive"))
    )
    (net (code "63") (name "/MCU_GPIO_PF9") (class "Default")
      (node (ref "U5") (pin "21") (pinfunction "PF9_21") (pintype "passive"))
    )
    (net (code "64") (name "/MCU_GPIO_PF10") (class "Default")
      (node (ref "U5") (pin "22") (pinfunction "PF10_22") (pintype "passive"))
    )
    (net (code "65") (name "/MCU_GPIO_PF11") (class "Default")
      (node (ref "U5") (pin "49") (pinfunction "PF11_49") (pintype "passive"))
    )
    (net (code "66") (name "/MCU_GPIO_PF12") (class "Default")
      (node (ref "U5") (pin "50") (pinfunction "PF12_50") (pintype "passive"))
    )
    (net (code "67") (name "/MCU_GPIO_PF13") (class "Default")
      (node (ref "U5") (pin "53") (pinfunction "PF13_53") (pintype "passive"))
    )
    (net (code "68") (name "/MCU_GPIO_PF14") (class "Default")
      (node (ref "U5") (pin "54") (pinfunction "PF14_54") (pintype "passive"))
    )
    (net (code "69") (name "/MCU_SER_RXD") (class "Default")
      (node (ref "P9") (pin "5") (pinfunction "5_5") (pintype "passive"))
      (node (ref "U5") (pin "142") (pinfunction "PE1_142") (pintype "passive"))
      (node (ref "U8") (pin "4") (pinfunction "C_4") (pintype "passive"))
    )
    (net (code "70") (name "/MCU_SER_TXD") (class "Default")
      (node (ref "P9") (pin "4") (pinfunction "4_4") (pintype "passive"))
      (node (ref "U5") (pin "141") (pinfunction "PE0_141") (pintype "passive"))
      (node (ref "U8") (pin "6") (pinfunction "D_6") (pintype "passive"))
    )
    (net (code "71") (name "/MCU_SPI3_MOSI") (class "Default")
      (node (ref "U5") (pin "48") (pinfunction "PB2_48") (pintype "passive"))
    )
    (net (code "72") (name "/MCU_SPI3_SCLK") (class "Default")
      (node (ref "U5") (pin "111") (pinfunction "PC10_111") (pintype "passive"))
    )
    (net (code "73") (name "/MCU_SWCLK") (class "Default")
      (node (ref "R34") (pin "1") (pinfunction "1_1") (pintype "passive"))
      (node (ref "U5") (pin "109") (pinfunction "PA14_109") (pintype "passive"))
    )
    (net (code "74") (name "/MCU_SWDIO") (class "Default")
      (node (ref "R35") (pin "1") (pinfunction "1_1") (pintype "passive"))
      (node (ref "U5") (pin "105") (pinfunction "PA13_105") (pintype "passive"))
    )
    (net (code "75") (name "/MCU_TDI") (class "Default")
      (node (ref "U5") (pin "110") (pinfunction "PA15_110") (pintype "passive"))
    )
    (net (code "76") (name "/MCU_TRACESWO") (class "Default")
      (node (ref "R33") (pin "1") (pinfunction "1_1") (pintype "passive"))
      (node (ref "U5") (pin "133") (pinfunction "PB3_133") (pintype "passive"))
    )
    (net (code "77") (name "/SLO_I2C1_SCL") (class "Default")
      (node (ref "U5") (pin "136") (pinfunction "PB6_136") (pintype "passive"))
    )
    (net (code "78") (name "/SLO_I2C1_SDA") (class "Default")
      (node (ref "U5") (pin "137") (pinfunction "PB7_137") (pintype "passive"))
    )
    (net (code "79") (name "/SLO_I2C4_SCL") (class "Default")
      (node (ref "U5") (pin "81") (pinfunction "PD12_81") (pintype "passive"))
    )
    (net (code "80") (name "/SLO_I2C4_SDA") (class "Default")
      (node (ref "U5") (pin "82") (pinfunction "PD13_82") (pintype "passive"))
    )
    (net (code "81") (name "GND") (class "Default")
      (node (ref "C40") (pin "2") (pinfunction "2_2") (pintype "passive"))
      (node (ref "C41") (pin "1") (pinfunction "1_1") (pintype "passive"))
      (node (ref "C42") (pin "1") (pinfunction "1_1") (pintype "passive"))
      (node (ref "C43") (pin "1") (pinfunction "1_1") (pintype "passive"))
      (node (ref "C44") (pin "1") (pinfunction "1_1") (pintype "passive"))
      (node (ref "C45") (pin "1") (pinfunction "1_1") (pintype "passive"))
      (node (ref "C46") (pin "1") (pinfunction "1_1") (pintype "passive"))
      (node (ref "C47") (pin "1") (pinfunction "1_1") (pintype "passive"))
      (node (ref "C48") (pin "1") (pinfunction "1_1") (pintype "passive"))
      (node (ref "C49") (pin "1") (pinfunction "1_1") (pintype "passive"))
      (node (ref "C50") (pin "1") (pinfunction "1_1") (pintype "passive"))
      (node (ref "C51") (pin "1") (pinfunction "1_1") (pintype "passive"))
      (node (ref "C52") (pin "1") (pinfunction "1_1") (pintype "passive"))
      (node (ref "C53") (pin "1") (pinfunction "1_1") (pintype "passive"))
      (node (ref "C54") (pin "1") (pinfunction "1_1") (pintype "passive"))
      (node (ref "C55") (pin "1") (pinfunction "1_1") (pintype "passive"))
      (node (ref "C56") (pin "1") (pinfunction "1_1") (pintype "passive"))
      (node (ref "C57") (pin "1") (pinfunction "1_1") (pintype "passive"))
      (node (ref "C58") (pin "1") (pinfunction "1_1") (pintype "passive"))
      (node (ref "C59") (pin "1") (pinfunction "1_1") (pintype "passive"))
      (node (ref "C60") (pin "1") (pinfunction "1_1") (pintype "passive"))
      (node (ref "C61") (pin "1") (pinfunction "1_1") (pintype "passive"))
      (node (ref "C62") (pin "2") (pinfunction "2_2") (pintype "passive"))
      (node (ref "C63") (pin "2") (pinfunction "2_2") (pintype "passive"))
      (node (ref "C64") (pin "2") (pinfunction "2_2") (pintype "passive"))
      (node (ref "C65") (pin "2") (pinfunction "2_2") (pintype "passive"))
      (node (ref "C66") (pin "2") (pinfunction "2_2") (pintype "passive"))
      (node (ref "C67") (pin "2") (pinfunction "2_2") (pintype "passive"))
      (node (ref "ID0") (pin "2") (pinfunction "2_2") (pintype "passive"))
      (node (ref "ID1") (pin "2") (pinfunction "2_2") (pintype "passive"))
      (node (ref "ID2") (pin "2") (pinfunction "2_2") (pintype "passive"))
      (node (ref "ID3") (pin "2") (pinfunction "2_2") (pintype "passive"))
      (node (ref "P10") (pin "3") (pinfunction "3_3") (pintype "passive"))
      (node (ref "P9") (pin "1") (pinfunction "1_1") (pintype "passive"))
      (node (ref "R21") (pin "2") (pinfunction "2_2") (pintype "passive"))
      (node (ref "R24") (pin "2") (pinfunction "2_2") (pintype "passive"))
      (node (ref "R31") (pin "2") (pinfunction "2_2") (pintype "passive"))
      (node (ref "U4") (pin "10") (pinfunction "VSS_10") (pintype "power_in"))
      (node (ref "U5") (pin "107") (pinfunction "VSS_2_107") (pintype "passive"))
      (node (ref "U5") (pin "120") (pinfunction "VSS_10_120") (pintype "passive"))
      (node (ref "U5") (pin "130") (pinfunction "VSS_11/VSSIO_2_130") (pintype "passive"))
      (node (ref "U5") (pin "143") (pinfunction "PDR_ON/VSS_3/NC_143") (pintype "passive"))
      (node (ref "U5") (pin "16") (pinfunction "VSS_5_16") (pintype "passive"))
      (node (ref "U5") (pin "31") (pinfunction "VSSA/VREF-_31") (pintype "passive"))
      (node (ref "U5") (pin "38") (pinfunction "VSS_4/BYPASS_REG_38") (pintype "passive"))
      (node (ref "U5") (pin "51") (pinfunction "VSS_6_51") (pintype "passive"))
      (node (ref "U5") (pin "61") (pinfunction "VSS_7_61") (pintype "passive"))
      (node (ref "U5") (pin "83") (pinfunction "VSS_8_83") (pintype "passive"))
      (node (ref "U5") (pin "94") (pinfunction "VSS_9/VSSIO_1_94") (pintype "passive"))
      (node (ref "U6") (pin "2") (pinfunction "GND_2") (pintype "power_in"))
      (node (ref "U7") (pin "4") (pinfunction "GND_4") (pintype "power_in"))
      (node (ref "U7") (pin "5") (pinfunction "DIR_5") (pintype "input"))
      (node (ref "U8") (pin "2") (pinfunction "G_2") (pintype "power_in"))
      (node (ref "U9") (pin "2") (pinfunction "GND_2") (pintype "power_in"))
    )
    (net (code "82") (name "Net-(P10-Pad2)") (class "Default")
      (node (ref "P10") (pin "2") (pinfunction "2_2") (pintype "passive"))
      (node (ref "R34") (pin "2") (pinfunction "2_2") (pintype "passive"))
    )
    (net (code "83") (name "Net-(P10-Pad4)") (class "Default")
      (node (ref "P10") (pin "4") (pinfunction "4_4") (pintype "passive"))
      (node (ref "R35") (pin "2") (pinfunction "2_2") (pintype "passive"))
    )
    (net (code "84") (name "Net-(P10-Pad5)") (class "Default")
      (node (ref "P10") (pin "5") (pinfunction "5_5") (pintype "passive"))
      (node (ref "R36") (pin "2") (pinfunction "2_2") (pintype "passive"))
    )
    (net (code "85") (name "Net-(P10-Pad6)") (class "Default")
      (node (ref "P10") (pin "6") (pinfunction "6_6") (pintype "passive"))
      (node (ref "R33") (pin "2") (pinfunction "2_2") (pintype "passive"))
    )
    (net (code "86") (name "Net-(U4A-IO3{slash}RESET#)") (class "Default")
      (node (ref "R23") (pin "1") (pinfunction "1_1") (pintype "passive"))
      (node (ref "U4") (pin "1") (pinfunction "IO3/RESET#_1") (pintype "bidirectional"))
    )
    (net (code "87") (name "Net-(U5A-PC8)") (class "Default")
      (node (ref "ID0") (pin "1") (pinfunction "1_1") (pintype "passive"))
      (node (ref "U5") (pin "98") (pinfunction "PC8_98") (pintype "passive"))
    )
    (net (code "88") (name "Net-(U5A-PC9)") (class "Default")
      (node (ref "ID1") (pin "1") (pinfunction "1_1") (pintype "passive"))
      (node (ref "U5") (pin "99") (pinfunction "PC9_99") (pintype "passive"))
    )
    (net (code "89") (name "Net-(U5A-PC11)") (class "Default")
      (node (ref "ID2") (pin "1") (pinfunction "1_1") (pintype "passive"))
      (node (ref "U5") (pin "112") (pinfunction "PC11_112") (pintype "passive"))
    )
    (net (code "90") (name "Net-(U5A-PC12)") (class "Default")
      (node (ref "ID3") (pin "1") (pinfunction "1_1") (pintype "passive"))
      (node (ref "U5") (pin "113") (pinfunction "PC12_113") (pintype "passive"))
    )
    (net (code "91") (name "Net-(U5B-PG4)") (class "Default")
      (node (ref "R27") (pin "1") (pinfunction "1_1") (pintype "passive"))
      (node (ref "U5") (pin "89") (pinfunction "PG4_89") (pintype "passive"))
    )
    (net (code "92") (name "Net-(U5B-PG5)") (class "Default")
      (node (ref "R28") (pin "1") (pinfunction "1_1") (pintype "passive"))
      (node (ref "U5") (pin "90") (pinfunction "PG5_90") (pintype "passive"))
    )
    (net (code "93") (name "Net-(U5B-PG6)") (class "Default")
      (node (ref "R29") (pin "1") (pinfunction "1_1") (pintype "passive"))
      (node (ref "U5") (pin "91") (pinfunction "PG6_91") (pintype "passive"))
    )
    (net (code "94") (name "Net-(U5B-PG7)") (class "Default")
      (node (ref "R30") (pin "1") (pinfunction "1_1") (pintype "passive"))
      (node (ref "U5") (pin "92") (pinfunction "PG7_92") (pintype "passive"))
    )
    (net (code "95") (name "Net-(U5C-VCAP1{slash}VSS_1)") (class "Default")
      (node (ref "C52") (pin "2") (pinfunction "2_2") (pintype "passive"))
      (node (ref "U5") (pin "71") (pinfunction "VCAP1/VSS_1_71") (pintype "passive"))
    )
    (net (code "96") (name "Net-(U5C-VCAP2{slash}PH2{slash}VDDUSB)") (class "Default")
      (node (ref "C53") (pin "2") (pinfunction "2_2") (pintype "passive"))
      (node (ref "U5") (pin "106") (pinfunction "VCAP2/PH2/VDDUSB_106") (pintype "passive"))
    )
    (net (code "97") (name "Net-(U6-TTLOUT)") (class "Default")
      (node (ref "R25") (pin "1") (pinfunction "1_1") (pintype "passive"))
      (node (ref "U6") (pin "5") (pinfunction "TTLOUT_5") (pintype "output"))
    )
    (net (code "98") (name "Net-(U9-TTLOUT)") (class "Default")
      (node (ref "R26") (pin "1") (pinfunction "1_1") (pintype "passive"))
      (node (ref "U9") (pin "5") (pinfunction "TTLOUT_5") (pintype "output"))
    )
    (net (code "99") (name "unconnected-(P9-Pad2)") (class "Default")
      (node (ref "P9") (pin "2") (pinfunction "2_2") (pintype "passive"))
    )
    (net (code "100") (name "unconnected-(P9-Pad6)") (class "Default")
      (node (ref "P9") (pin "6") (pinfunction "6_6") (pintype "passive"))
    )
    (net (code "101") (name "unconnected-(U4B-DNU-Pad11)") (class "Default")
      (node (ref "U4") (pin "11") (pinfunction "DNU_11") (pintype "passive"))
    )
    (net (code "102") (name "unconnected-(U4B-DNU-Pad12)") (class "Default")
      (node (ref "U4") (pin "12") (pinfunction "DNU_12") (pintype "passive"))
    )
    (net (code "103") (name "unconnected-(U4B-DNU-Pad13)") (class "Default")
      (node (ref "U4") (pin "13") (pinfunction "DNU_13") (pintype "passive"))
    )
    (net (code "104") (name "unconnected-(U4B-NC-Pad4)") (class "Default")
      (node (ref "U4") (pin "4") (pinfunction "NC_4") (pintype "passive"))
    )
    (net (code "105") (name "unconnected-(U4B-NC-Pad5)") (class "Default")
      (node (ref "U4") (pin "5") (pinfunction "NC_5") (pintype "passive"))
    )
    (net (code "106") (name "unconnected-(U4B-RFU-Pad3)") (class "Default")
      (node (ref "U4") (pin "3") (pinfunction "RFU_3") (pintype "passive"))
    )
    (net (code "107") (name "unconnected-(U4B-RFU-Pad6)") (class "Default")
      (node (ref "U4") (pin "6") (pinfunction "RFU_6") (pintype "passive"))
    )
    (net (code "108") (name "unconnected-(U4B-RFU-Pad14)") (class "Default")
      (node (ref "U4") (pin "14") (pinfunction "RFU_14") (pintype "passive"))
    )
    (net (code "109") (name "unconnected-(U5A-PA6-Pad42)") (class "Default")
      (node (ref "U5") (pin "42") (pinfunction "PA6_42") (pintype "passive"))
    )
    (net (code "110") (name "unconnected-(U5A-PA10-Pad102)") (class "Default")
      (node (ref "U5") (pin "102") (pinfunction "PA10_102") (pintype "passive"))
    )
    (net (code "111") (name "unconnected-(U5A-PB0-Pad46)") (class "Default")
      (node (ref "U5") (pin "46") (pinfunction "PB0_46") (pintype "passive"))
    )
    (net (code "112") (name "unconnected-(U5A-PB1-Pad47)") (class "Default")
      (node (ref "U5") (pin "47") (pinfunction "PB1_47") (pintype "passive"))
    )
    (net (code "113") (name "unconnected-(U5A-PC0-Pad26)") (class "Default")
      (node (ref "U5") (pin "26") (pinfunction "PC0_26") (pintype "passive"))
    )
    (net (code "114") (name "unconnected-(U5A-PC6-Pad96)") (class "Default")
      (node (ref "U5") (pin "96") (pinfunction "PC6_96") (pintype "passive"))
    )
    (net (code "115") (name "unconnected-(U5A-PC13-Pad7)") (class "Default")
      (node (ref "U5") (pin "7") (pinfunction "PC13_7") (pintype "passive"))
    )
    (net (code "116") (name "unconnected-(U5A-PC14-OSC32_IN-Pad8)") (class "Default")
      (node (ref "U5") (pin "8") (pinfunction "PC14-OSC32_IN_8") (pintype "passive"))
    )
    (net (code "117") (name "unconnected-(U5A-PC15-OSC32_OUT-Pad9)") (class "Default")
      (node (ref "U5") (pin "9") (pinfunction "PC15-OSC32_OUT_9") (pintype "passive"))
    )
    (net (code "118") (name "unconnected-(U5B-PD0-Pad114)") (class "Default")
      (node (ref "U5") (pin "114") (pinfunction "PD0_114") (pintype "passive"))
    )
    (net (code "119") (name "unconnected-(U5B-PD1-Pad115)") (class "Default")
      (node (ref "U5") (pin "115") (pinfunction "PD1_115") (pintype "passive"))
    )
    (net (code "120") (name "unconnected-(U5B-PD2-Pad116)") (class "Default")
      (node (ref "U5") (pin "116") (pinfunction "PD2_116") (pintype "passive"))
    )
    (net (code "121") (name "unconnected-(U5B-PD3-Pad117)") (class "Default")
      (node (ref "U5") (pin "117") (pinfunction "PD3_117") (pintype "passive"))
    )
    (net (code "122") (name "unconnected-(U5B-PD4-Pad118)") (class "Default")
      (node (ref "U5") (pin "118") (pinfunction "PD4_118") (pintype "passive"))
    )
    (net (code "123") (name "unconnected-(U5B-PD5-Pad119)") (class "Default")
      (node (ref "U5") (pin "119") (pinfunction "PD5_119") (pintype "passive"))
    )
    (net (code "124") (name "unconnected-(U5B-PD6-Pad122)") (class "Default")
      (node (ref "U5") (pin "122") (pinfunction "PD6_122") (pintype "passive"))
    )
    (net (code "125") (name "unconnected-(U5B-PD7-Pad123)") (class "Default")
      (node (ref "U5") (pin "123") (pinfunction "PD7_123") (pintype "passive"))
    )
    (net (code "126") (name "unconnected-(U5B-PD8-Pad77)") (class "Default")
      (node (ref "U5") (pin "77") (pinfunction "PD8_77") (pintype "passive"))
    )
    (net (code "127") (name "unconnected-(U5B-PD9-Pad78)") (class "Default")
      (node (ref "U5") (pin "78") (pinfunction "PD9_78") (pintype "passive"))
    )
    (net (code "128") (name "unconnected-(U5B-PD10-Pad79)") (class "Default")
      (node (ref "U5") (pin "79") (pinfunction "PD10_79") (pintype "passive"))
    )
    (net (code "129") (name "unconnected-(U5B-PD11-Pad80)") (class "Default")
      (node (ref "U5") (pin "80") (pinfunction "PD11_80") (pintype "passive"))
    )
    (net (code "130") (name "unconnected-(U5B-PD14-Pad85)") (class "Default")
      (node (ref "U5") (pin "85") (pinfunction "PD14_85") (pintype "passive"))
    )
    (net (code "131") (name "unconnected-(U5B-PD15-Pad86)") (class "Default")
      (node (ref "U5") (pin "86") (pinfunction "PD15_86") (pintype "passive"))
    )
    (net (code "132") (name "unconnected-(U5B-PE3-Pad2)") (class "Default")
      (node (ref "U5") (pin "2") (pinfunction "PE3_2") (pintype "passive"))
    )
    (net (code "133") (name "unconnected-(U5B-PE11-Pad64)") (class "Default")
      (node (ref "U5") (pin "64") (pinfunction "PE11_64") (pintype "passive"))
    )
    (net (code "134") (name "unconnected-(U5B-PE12-Pad65)") (class "Default")
      (node (ref "U5") (pin "65") (pinfunction "PE12_65") (pintype "passive"))
    )
    (net (code "135") (name "unconnected-(U5B-PE13-Pad66)") (class "Default")
      (node (ref "U5") (pin "66") (pinfunction "PE13_66") (pintype "passive"))
    )
    (net (code "136") (name "unconnected-(U5B-PE14-Pad67)") (class "Default")
      (node (ref "U5") (pin "67") (pinfunction "PE14_67") (pintype "passive"))
    )
    (net (code "137") (name "unconnected-(U5B-PE15-Pad68)") (class "Default")
      (node (ref "U5") (pin "68") (pinfunction "PE15_68") (pintype "passive"))
    )
    (net (code "138") (name "unconnected-(U5B-PF15-Pad55)") (class "Default")
      (node (ref "U5") (pin "55") (pinfunction "PF15_55") (pintype "passive"))
    )
    (net (code "139") (name "unconnected-(U5B-PG0-Pad56)") (class "Default")
      (node (ref "U5") (pin "56") (pinfunction "PG0_56") (pintype "passive"))
    )
    (net (code "140") (name "unconnected-(U5B-PG1-Pad57)") (class "Default")
      (node (ref "U5") (pin "57") (pinfunction "PG1_57") (pintype "passive"))
    )
    (net (code "141") (name "unconnected-(U5B-PG2-Pad87)") (class "Default")
      (node (ref "U5") (pin "87") (pinfunction "PG2_87") (pintype "passive"))
    )
    (net (code "142") (name "unconnected-(U5B-PG3-Pad88)") (class "Default")
      (node (ref "U5") (pin "88") (pinfunction "PG3_88") (pintype "passive"))
    )
    (net (code "143") (name "unconnected-(U5B-PG9-Pad124)") (class "Default")
      (node (ref "U5") (pin "124") (pinfunction "PG9_124") (pintype "passive"))
    )
    (net (code "144") (name "unconnected-(U5B-PG10-Pad125)") (class "Default")
      (node (ref "U5") (pin "125") (pinfunction "PG10_125") (pintype "passive"))
    )
    (net (code "145") (name "unconnected-(U5B-PG11-Pad126)") (class "Default")
      (node (ref "U5") (pin "126") (pinfunction "PG11_126") (pintype "passive"))
    )
    (net (code "146") (name "unconnected-(U5B-PG13-Pad128)") (class "Default")
      (node (ref "U5") (pin "128") (pinfunction "PG13_128") (pintype "passive"))
    )
    (net (code "147") (name "unconnected-(U5B-PG14-Pad129)") (class "Default")
      (node (ref "U5") (pin "129") (pinfunction "PG14_129") (pintype "passive"))
    )
    (net (code "148") (name "unconnected-(U5B-PG15-Pad132)") (class "Default")
      (node (ref "U5") (pin "132") (pinfunction "PG15_132") (pintype "passive"))
    )
    (net (code "149") (name "unconnected-(U5C-PH1{slash}PF1-OSC_OUT-Pad24)") (class "Default")
      (node (ref "U5") (pin "24") (pinfunction "PH1/PF1-OSC_OUT_24") (pintype "passive"))
    )
    (net (code "150") (name "unconnected-(U8-A-Pad1)") (class "Default")
      (node (ref "U8") (pin "1") (pinfunction "A_1") (pintype "passive"))
    )
    (net (code "151") (name "unconnected-(U8-B-Pad3)") (class "Default")
      (node (ref "U8") (pin "3") (pinfunction "B_3") (pintype "passive"))
    )
  )
)
